# ethernet_adapter_stepper_2.net
KiCad netlist of a schematic drawn in EAGLE
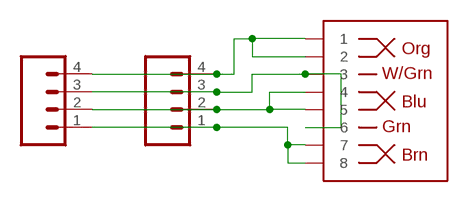
[diagram p0: schematic, sheet 1]

(export (version "E")
  (design (tool "Eeschema 10.0.6"))
  (components
    (comp (ref "J1")
      (value "RJ45")
      (footprint "eagle-import:RJ45-8")
      (libsource (lib "eagle-import") (part "RJ45-8"))
    )
    (comp (ref "J2")
      (value "CONN_04")
      (footprint "eagle-import:1X04")
      (libsource (lib "eagle-import") (part "CONN_04"))
    )
    (comp (ref "J4")
      (value "CONN_04SCREW")
      (footprint "eagle-import:SCREWTERMINAL-3.5MM-4")
      (libsource (lib "eagle-import") (part "CONN_04SCREW"))
    )
  )
  (nets
    (net (code "1") (name "Net-(J1-Pad1)") (class "Default")
      (node (ref "J1") (pin "1") (pinfunction "1_1") (pintype "bidirectional"))
      (node (ref "J1") (pin "2") (pinfunction "2_2") (pintype "bidirectional"))
      (node (ref "J2") (pin "4") (pinfunction "4_4") (pintype "passive"))
      (node (ref "J4") (pin "4") (pinfunction "4_4") (pintype "passive"))
    )
    (net (code "2") (name "Net-(J1-Pad3)") (class "Default")
      (node (ref "J1") (pin "3") (pinfunction "3_3") (pintype "bidirectional"))
      (node (ref "J1") (pin "6") (pinfunction "6_6") (pintype "bidirectional"))
      (node (ref "J2") (pin "3") (pinfunction "3_3") (pintype "passive"))
      (node (ref "J4") (pin "3") (pinfunction "3_3") (pintype "passive"))
    )
    (net (code "3") (name "Net-(J1-Pad4)") (class "Default")
      (node (ref "J1") (pin "4") (pinfunction "4_4") (pintype "bidirectional"))
      (node (ref "J1") (pin "5") (pinfunction "5_5") (pintype "bidirectional"))
      (node (ref "J2") (pin "2") (pinfunction "2_2") (pintype "passive"))
      (node (ref "J4") (pin "2") (pinfunction "2_2") (pintype "passive"))
    )
    (net (code "4") (name "Net-(J1-Pad7)") (class "Default")
      (node (ref "J1") (pin "7") (pinfunction "7_7") (pintype "bidirectional"))
      (node (ref "J1") (pin "8") (pinfunction "8_8") (pintype "bidirectional"))
      (node (ref "J2") (pin "1") (pinfunction "1_1") (pintype "passive"))
      (node (ref "J4") (pin "1") (pinfunction "1_1") (pintype "passive"))
    )
  )
)
